# Circuit.net
KiCad netlist of a schematic drawn in EAGLE
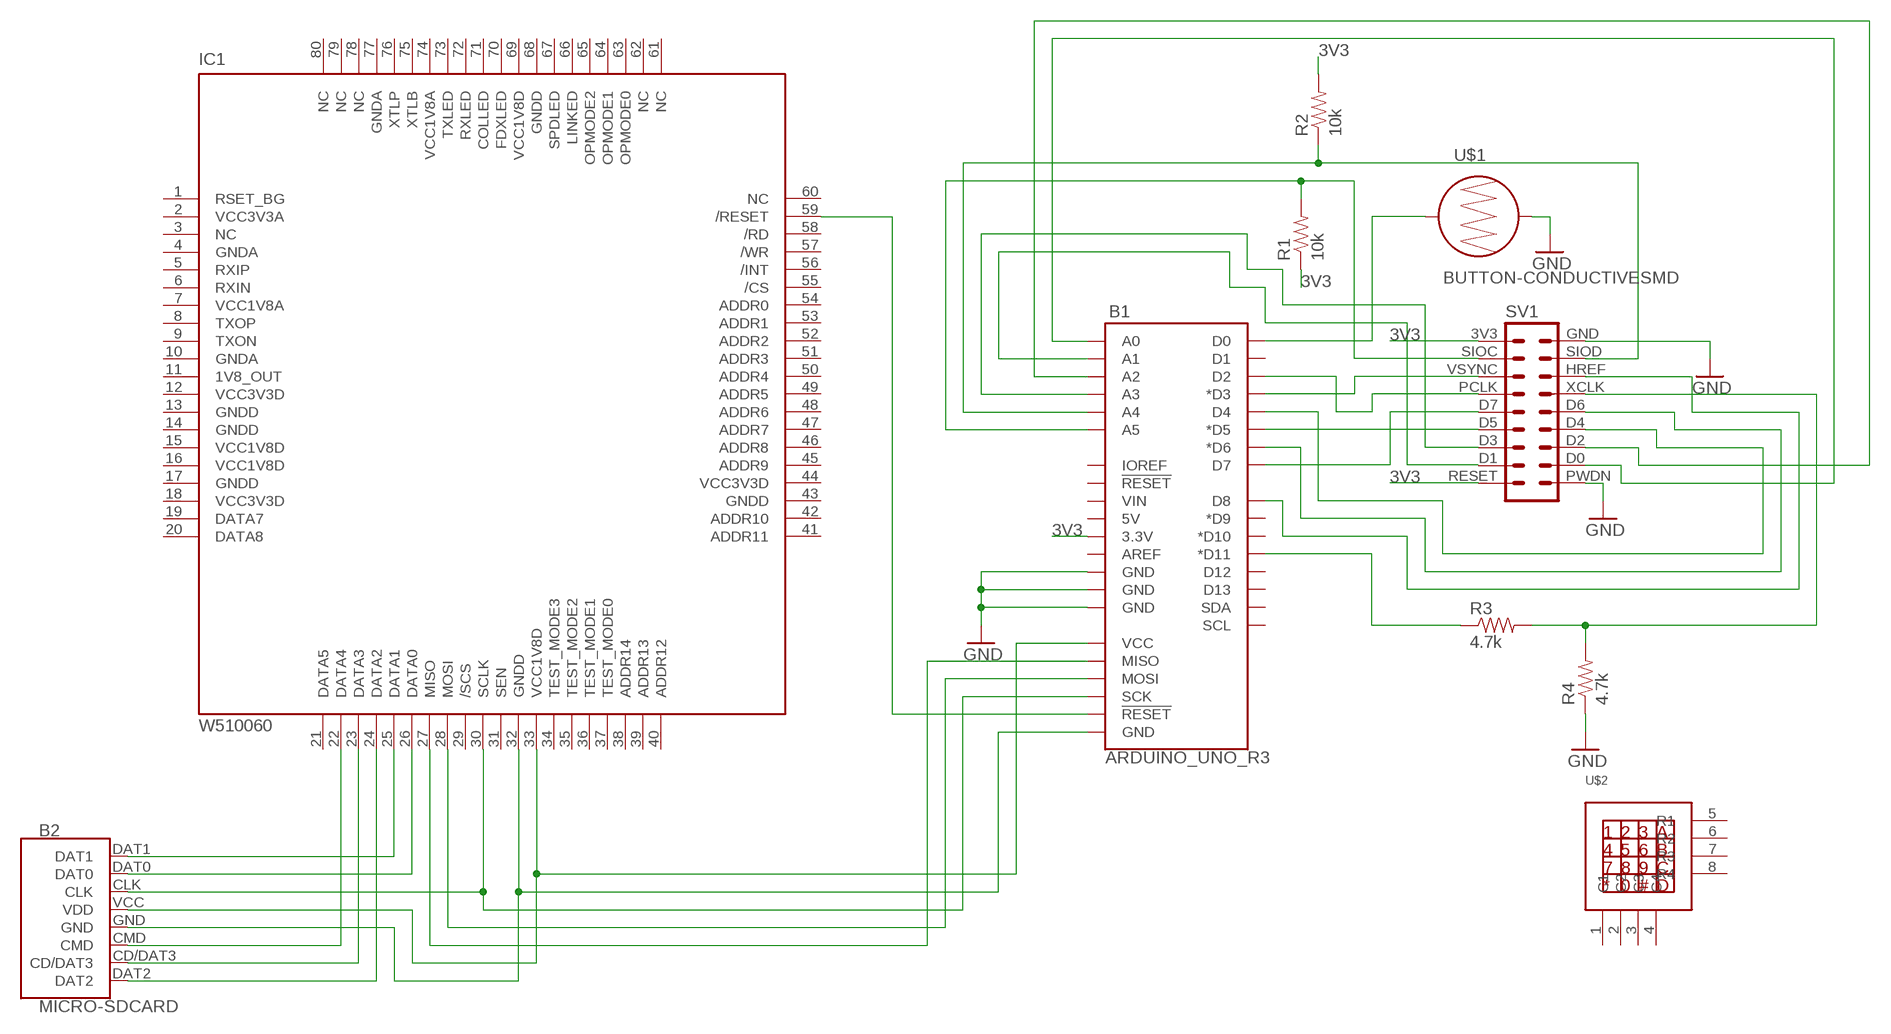
[diagram p0: schematic, sheet 1]

(export (version "E")
  (design (tool "Eeschema 10.0.6"))
  (components
    (comp (ref "B1")
      (value "ARDUINO_UNO_R3")
      (footprint "eagle-import:ARDUINO_R3")
      (libsource (lib "eagle-import") (part "ARDUINO_UNO_R3"))
    )
    (comp (ref "B2")
      (value "MICRO-SDCARD")
      (footprint "eagle-import:MICRO-SDCARD")
      (libsource (lib "eagle-import") (part "MICRO-SDCARD"))
    )
    (comp (ref "IC1")
      (value "W510060")
      (footprint "eagle-import:W5100")
      (fields (field (name "MPN") "PIC18F86J60-I/PT"))
      (libsource (lib "eagle-import") (part "W510006"))
    )
    (comp (ref "R1")
      (value "10k")
      (footprint "eagle-import:0402-RES")
      (libsource (lib "eagle-import") (part "RESISTOR0402"))
    )
    (comp (ref "R2")
      (value "10k")
      (footprint "eagle-import:0402-RES")
      (libsource (lib "eagle-import") (part "RESISTOR0402"))
    )
    (comp (ref "R3")
      (value "4.7k")
      (footprint "eagle-import:0402-RES")
      (libsource (lib "eagle-import") (part "RESISTOR0402"))
    )
    (comp (ref "R4")
      (value "4.7k")
      (footprint "eagle-import:0402-RES")
      (libsource (lib "eagle-import") (part "RESISTOR0402"))
    )
    (comp (ref "SV1")
      (value "ML16L")
      (footprint "eagle-import:ML16L")
      (libsource (lib "eagle-import") (part "ML16L"))
    )
    (comp (ref "U$1")
      (value "BUTTON-CONDUCTIVESMD")
      (footprint "eagle-import:BUTTON-CONDUCTIVE")
      (libsource (lib "eagle-import") (part "BUTTON-CONDUCTIVESMD"))
    )
    (comp (ref "U$2")
      (value "KEYPAD4X4")
      (footprint "eagle-import:KEYPAD4X4")
      (libsource (lib "eagle-import") (part "KEYPAD4X4"))
    )
  )
  (nets
    (net (code "1") (name "/1V8_OUT") (class "Default")
      (node (ref "IC1") (pin "11") (pinfunction "1V8_OUT_11") (pintype "power_in"))
    )
    (net (code "2") (name "/3V3") (class "Default")
      (node (ref "B1") (pin "3.3V") (pinfunction "3.3V_3.3V") (pintype "bidirectional"))
      (node (ref "R1") (pin "1") (pinfunction "1_1") (pintype "passive"))
      (node (ref "R2") (pin "2") (pinfunction "2_2") (pintype "passive"))
      (node (ref "SV1") (pin "3V3") (pinfunction "3V3_3V3") (pintype "passive"))
      (node (ref "SV1") (pin "RESET") (pinfunction "RESET_RESET") (pintype "passive"))
    )
    (net (code "3") (name "/ADDR3") (class "Default")
      (node (ref "IC1") (pin "51") (pinfunction "ADDR3_51") (pintype "power_in"))
    )
    (net (code "4") (name "/ADDR6") (class "Default")
      (node (ref "IC1") (pin "48") (pinfunction "ADDR6_48") (pintype "power_in"))
    )
    (net (code "5") (name "/COLLED") (class "Default")
      (node (ref "IC1") (pin "71") (pinfunction "COLLED_71") (pintype "power_in"))
    )
    (net (code "6") (name "/FDXLED") (class "Default")
      (node (ref "IC1") (pin "70") (pinfunction "FDXLED_70") (pintype "power_in"))
    )
    (net (code "7") (name "/SEN") (class "Default")
      (node (ref "IC1") (pin "31") (pinfunction "SEN_31") (pintype "power_in"))
    )
    (net (code "8") (name "GND") (class "Default")
      (node (ref "B1") (pin "GND@2") (pinfunction "GND_GND@2") (pintype "bidirectional"))
      (node (ref "B1") (pin "GND@3") (pinfunction "GND_GND@3") (pintype "bidirectional"))
      (node (ref "B1") (pin "GND@4") (pinfunction "GND_GND@4") (pintype "bidirectional"))
      (node (ref "R4") (pin "1") (pinfunction "1_1") (pintype "passive"))
      (node (ref "SV1") (pin "GND") (pinfunction "GND_GND") (pintype "passive"))
      (node (ref "SV1") (pin "PWDN") (pinfunction "PWDN_PWDN") (pintype "passive"))
      (node (ref "U$1") (pin "2") (pinfunction "2_2") (pintype "passive"))
    )
    (net (code "9") (name "Net-(B1-*D3)") (class "Default")
      (node (ref "B1") (pin "D3") (pinfunction "*D3_D3") (pintype "bidirectional"))
      (node (ref "SV1") (pin "VSYNC") (pinfunction "VSYNC_VSYNC") (pintype "passive"))
    )
    (net (code "10") (name "Net-(B1-*D5)") (class "Default")
      (node (ref "B1") (pin "D5") (pinfunction "*D5_D5") (pintype "bidirectional"))
      (node (ref "SV1") (pin "D5") (pinfunction "D5_D5") (pintype "passive"))
    )
    (net (code "11") (name "Net-(B1-*D6)") (class "Default")
      (node (ref "B1") (pin "D6") (pinfunction "*D6_D6") (pintype "bidirectional"))
      (node (ref "SV1") (pin "D6") (pinfunction "D6_D6") (pintype "passive"))
    )
    (net (code "12") (name "Net-(B1-*D11)") (class "Default")
      (node (ref "B1") (pin "D11") (pinfunction "*D11_D11") (pintype "bidirectional"))
      (node (ref "R3") (pin "1") (pinfunction "1_1") (pintype "passive"))
    )
    (net (code "13") (name "Net-(B1-GND-PadGND@1)") (class "Default")
      (node (ref "B1") (pin "GND@1") (pinfunction "GND_GND@1") (pintype "bidirectional"))
      (node (ref "B2") (pin "GND") (pinfunction "GND_GND") (pintype "power_in"))
      (node (ref "IC1") (pin "32") (pinfunction "GNDD_32") (pintype "power_in"))
    )
    (net (code "14") (name "Net-(B1-PadA0)") (class "Default")
      (node (ref "B1") (pin "A0") (pinfunction "A0_A0") (pintype "bidirectional"))
      (node (ref "SV1") (pin "D0") (pinfunction "D0_D0") (pintype "passive"))
    )
    (net (code "15") (name "Net-(B1-PadA1)") (class "Default")
      (node (ref "B1") (pin "A1") (pinfunction "A1_A1") (pintype "bidirectional"))
      (node (ref "SV1") (pin "D1") (pinfunction "D1_D1") (pintype "passive"))
    )
    (net (code "16") (name "Net-(B1-PadA2)") (class "Default")
      (node (ref "B1") (pin "A2") (pinfunction "A2_A2") (pintype "bidirectional"))
      (node (ref "SV1") (pin "D2") (pinfunction "D2_D2") (pintype "passive"))
    )
    (net (code "17") (name "Net-(B1-PadA3)") (class "Default")
      (node (ref "B1") (pin "A3") (pinfunction "A3_A3") (pintype "bidirectional"))
      (node (ref "SV1") (pin "D3") (pinfunction "D3_D3") (pintype "passive"))
    )
    (net (code "18") (name "Net-(B1-PadA4)") (class "Default")
      (node (ref "B1") (pin "A4") (pinfunction "A4_A4") (pintype "bidirectional"))
      (node (ref "R2") (pin "1") (pinfunction "1_1") (pintype "passive"))
      (node (ref "SV1") (pin "SIOD") (pinfunction "SIOD_SIOD") (pintype "passive"))
    )
    (net (code "19") (name "Net-(B1-PadA5)") (class "Default")
      (node (ref "B1") (pin "A5") (pinfunction "A5_A5") (pintype "bidirectional"))
      (node (ref "R1") (pin "2") (pinfunction "2_2") (pintype "passive"))
      (node (ref "SV1") (pin "SIOC") (pinfunction "SIOC_SIOC") (pintype "passive"))
    )
    (net (code "20") (name "Net-(B1-PadD0)") (class "Default")
      (node (ref "B1") (pin "D0") (pinfunction "D0_D0") (pintype "bidirectional"))
      (node (ref "U$1") (pin "1") (pinfunction "1_1") (pintype "passive"))
    )
    (net (code "21") (name "Net-(B1-PadD2)") (class "Default")
      (node (ref "B1") (pin "D2") (pinfunction "D2_D2") (pintype "bidirectional"))
      (node (ref "SV1") (pin "PCLK") (pinfunction "PCLK_PCLK") (pintype "passive"))
    )
    (net (code "22") (name "Net-(B1-PadD4)") (class "Default")
      (node (ref "B1") (pin "D4") (pinfunction "D4_D4") (pintype "bidirectional"))
      (node (ref "SV1") (pin "D4") (pinfunction "D4_D4") (pintype "passive"))
    )
    (net (code "23") (name "Net-(B1-PadD7)") (class "Default")
      (node (ref "B1") (pin "D7") (pinfunction "D7_D7") (pintype "bidirectional"))
      (node (ref "SV1") (pin "D7") (pinfunction "D7_D7") (pintype "passive"))
    )
    (net (code "24") (name "Net-(B1-PadD8)") (class "Default")
      (node (ref "B1") (pin "D8") (pinfunction "D8_D8") (pintype "bidirectional"))
      (node (ref "SV1") (pin "HREF") (pinfunction "HREF_HREF") (pintype "passive"))
    )
    (net (code "25") (name "Net-(B2-VDD)") (class "Default")
      (node (ref "B1") (pin "VCC") (pinfunction "VCC_VCC") (pintype "bidirectional"))
      (node (ref "B2") (pin "VCC") (pinfunction "VDD_VCC") (pintype "power_in"))
      (node (ref "IC1") (pin "33") (pinfunction "VCC1V8D_33") (pintype "bidirectional"))
    )
    (net (code "26") (name "Net-(IC1-DATA0)") (class "Default")
      (node (ref "B2") (pin "DAT0") (pinfunction "DAT0_DAT0") (pintype "bidirectional"))
      (node (ref "IC1") (pin "26") (pinfunction "DATA0_26") (pintype "input"))
    )
    (net (code "27") (name "Net-(IC1-DATA1)") (class "Default")
      (node (ref "B2") (pin "DAT1") (pinfunction "DAT1_DAT1") (pintype "bidirectional"))
      (node (ref "IC1") (pin "25") (pinfunction "DATA1_25") (pintype "input"))
    )
    (net (code "28") (name "Net-(IC1-DATA2)") (class "Default")
      (node (ref "B2") (pin "DAT2") (pinfunction "DAT2_DAT2") (pintype "bidirectional"))
      (node (ref "IC1") (pin "24") (pinfunction "DATA2_24") (pintype "input"))
    )
    (net (code "29") (name "Net-(IC1-DATA3)") (class "Default")
      (node (ref "B2") (pin "CD/DAT3") (pinfunction "CD/DAT3_CD/DAT3") (pintype "bidirectional"))
      (node (ref "IC1") (pin "23") (pinfunction "DATA3_23") (pintype "bidirectional"))
    )
    (net (code "30") (name "Net-(IC1-DATA4)") (class "Default")
      (node (ref "B2") (pin "CMD") (pinfunction "CMD_CMD") (pintype "bidirectional"))
      (node (ref "IC1") (pin "22") (pinfunction "DATA4_22") (pintype "bidirectional"))
    )
    (net (code "31") (name "Net-(IC1-MISO)") (class "Default")
      (node (ref "B1") (pin "MISO") (pinfunction "MISO_MISO") (pintype "bidirectional"))
      (node (ref "IC1") (pin "27") (pinfunction "MISO_27") (pintype "bidirectional"))
    )
    (net (code "32") (name "Net-(IC1-MOSI)") (class "Default")
      (node (ref "B1") (pin "MOSI") (pinfunction "MOSI_MOSI") (pintype "bidirectional"))
      (node (ref "IC1") (pin "28") (pinfunction "MOSI_28") (pintype "bidirectional"))
    )
    (net (code "33") (name "Net-(IC1-SCLK)") (class "Default")
      (node (ref "B1") (pin "SCK") (pinfunction "SCK_SCK") (pintype "bidirectional"))
      (node (ref "B2") (pin "CLK") (pinfunction "CLK_CLK") (pintype "bidirectional"))
      (node (ref "IC1") (pin "30") (pinfunction "SCLK_30") (pintype "bidirectional"))
    )
    (net (code "34") (name "Net-(IC1-{slash}RESET)") (class "Default")
      (node (ref "B1") (pin "RESET@2") (pinfunction "~{RESET}_RESET@2") (pintype "bidirectional"))
      (node (ref "IC1") (pin "59") (pinfunction "/RESET_59") (pintype "input"))
    )
    (net (code "35") (name "Net-(R3-Pad2)") (class "Default")
      (node (ref "R3") (pin "2") (pinfunction "2_2") (pintype "passive"))
      (node (ref "R4") (pin "2") (pinfunction "2_2") (pintype "passive"))
      (node (ref "SV1") (pin "XCLK") (pinfunction "XCLK_XCLK") (pintype "passive"))
    )
    (net (code "36") (name "unconnected-(B1-*D9-PadD9)") (class "Default")
      (node (ref "B1") (pin "D9") (pinfunction "*D9_D9") (pintype "bidirectional"))
    )
    (net (code "37") (name "unconnected-(B1-*D10-PadD10)") (class "Default")
      (node (ref "B1") (pin "D10") (pinfunction "*D10_D10") (pintype "bidirectional"))
    )
    (net (code "38") (name "unconnected-(B1-Pad5V)") (class "Default")
      (node (ref "B1") (pin "5V") (pinfunction "5V_5V") (pintype "bidirectional"))
    )
    (net (code "39") (name "unconnected-(B1-PadAREF)") (class "Default")
      (node (ref "B1") (pin "AREF") (pinfunction "AREF_AREF") (pintype "bidirectional"))
    )
    (net (code "40") (name "unconnected-(B1-PadD1)") (class "Default")
      (node (ref "B1") (pin "D1") (pinfunction "D1_D1") (pintype "bidirectional"))
    )
    (net (code "41") (name "unconnected-(B1-PadD12)") (class "Default")
      (node (ref "B1") (pin "D12") (pinfunction "D12_D12") (pintype "bidirectional"))
    )
    (net (code "42") (name "unconnected-(B1-PadD13)") (class "Default")
      (node (ref "B1") (pin "D13") (pinfunction "D13_D13") (pintype "bidirectional"))
    )
    (net (code "43") (name "unconnected-(B1-PadIOREF)") (class "Default")
      (node (ref "B1") (pin "IOREF") (pinfunction "IOREF_IOREF") (pintype "bidirectional"))
    )
    (net (code "44") (name "unconnected-(B1-PadSCL)") (class "Default")
      (node (ref "B1") (pin "SCL") (pinfunction "SCL_SCL") (pintype "bidirectional"))
    )
    (net (code "45") (name "unconnected-(B1-PadSDA)") (class "Default")
      (node (ref "B1") (pin "SDA") (pinfunction "SDA_SDA") (pintype "bidirectional"))
    )
    (net (code "46") (name "unconnected-(B1-PadVIN)") (class "Default")
      (node (ref "B1") (pin "VIN") (pinfunction "VIN_VIN") (pintype "bidirectional"))
    )
    (net (code "47") (name "unconnected-(B1-~{RESET}-PadRESET@1)") (class "Default")
      (node (ref "B1") (pin "RESET@1") (pinfunction "~{RESET}_RESET@1") (pintype "bidirectional"))
    )
    (net (code "48") (name "unconnected-(IC1-ADDR0-Pad54)") (class "Default")
      (node (ref "IC1") (pin "54") (pinfunction "ADDR0_54") (pintype "bidirectional"))
    )
    (net (code "49") (name "unconnected-(IC1-ADDR1-Pad53)") (class "Default")
      (node (ref "IC1") (pin "53") (pinfunction "ADDR1_53") (pintype "bidirectional"))
    )
    (net (code "50") (name "unconnected-(IC1-ADDR2-Pad52)") (class "Default")
      (node (ref "IC1") (pin "52") (pinfunction "ADDR2_52") (pintype "bidirectional"))
    )
    (net (code "51") (name "unconnected-(IC1-ADDR4-Pad50)") (class "Default")
      (node (ref "IC1") (pin "50") (pinfunction "ADDR4_50") (pintype "output"))
    )
    (net (code "52") (name "unconnected-(IC1-ADDR5-Pad49)") (class "Default")
      (node (ref "IC1") (pin "49") (pinfunction "ADDR5_49") (pintype "input"))
    )
    (net (code "53") (name "unconnected-(IC1-ADDR7-Pad47)") (class "Default")
      (node (ref "IC1") (pin "47") (pinfunction "ADDR7_47") (pintype "bidirectional"))
    )
    (net (code "54") (name "unconnected-(IC1-ADDR8-Pad46)") (class "Default")
      (node (ref "IC1") (pin "46") (pinfunction "ADDR8_46") (pintype "bidirectional"))
    )
    (net (code "55") (name "unconnected-(IC1-ADDR9-Pad45)") (class "Default")
      (node (ref "IC1") (pin "45") (pinfunction "ADDR9_45") (pintype "bidirectional"))
    )
    (net (code "56") (name "unconnected-(IC1-ADDR10-Pad42)") (class "Default")
      (node (ref "IC1") (pin "42") (pinfunction "ADDR10_42") (pintype "bidirectional"))
    )
    (net (code "57") (name "unconnected-(IC1-ADDR11-Pad41)") (class "Default")
      (node (ref "IC1") (pin "41") (pinfunction "ADDR11_41") (pintype "bidirectional"))
    )
    (net (code "58") (name "unconnected-(IC1-ADDR12-Pad40)") (class "Default")
      (node (ref "IC1") (pin "40") (pinfunction "ADDR12_40") (pintype "bidirectional"))
    )
    (net (code "59") (name "unconnected-(IC1-ADDR13-Pad39)") (class "Default")
      (node (ref "IC1") (pin "39") (pinfunction "ADDR13_39") (pintype "bidirectional"))
    )
    (net (code "60") (name "unconnected-(IC1-ADDR14-Pad38)") (class "Default")
      (node (ref "IC1") (pin "38") (pinfunction "ADDR14_38") (pintype "bidirectional"))
    )
    (net (code "61") (name "unconnected-(IC1-DATA5-Pad21)") (class "Default")
      (node (ref "IC1") (pin "21") (pinfunction "DATA5_21") (pintype "bidirectional"))
    )
    (net (code "62") (name "unconnected-(IC1-DATA7-Pad19)") (class "Default")
      (node (ref "IC1") (pin "19") (pinfunction "DATA7_19") (pintype "bidirectional"))
    )
    (net (code "63") (name "unconnected-(IC1-DATA8-Pad20)") (class "Default")
      (node (ref "IC1") (pin "20") (pinfunction "DATA8_20") (pintype "bidirectional"))
    )
    (net (code "64") (name "unconnected-(IC1-GNDA-Pad4)") (class "Default")
      (node (ref "IC1") (pin "4") (pinfunction "GNDA_4") (pintype "bidirectional"))
    )
    (net (code "65") (name "unconnected-(IC1-GNDA-Pad10)") (class "Default")
      (node (ref "IC1") (pin "10") (pinfunction "GNDA_10") (pintype "bidirectional"))
    )
    (net (code "66") (name "unconnected-(IC1-GNDA-Pad77)") (class "Default")
      (node (ref "IC1") (pin "77") (pinfunction "GNDA_77") (pintype "bidirectional"))
    )
    (net (code "67") (name "unconnected-(IC1-GNDD-Pad13)") (class "Default")
      (node (ref "IC1") (pin "13") (pinfunction "GNDD_13") (pintype "bidirectional"))
    )
    (net (code "68") (name "unconnected-(IC1-GNDD-Pad14)") (class "Default")
      (node (ref "IC1") (pin "14") (pinfunction "GNDD_14") (pintype "bidirectional"))
    )
    (net (code "69") (name "unconnected-(IC1-GNDD-Pad17)") (class "Default")
      (node (ref "IC1") (pin "17") (pinfunction "GNDD_17") (pintype "bidirectional"))
    )
    (net (code "70") (name "unconnected-(IC1-GNDD-Pad43)") (class "Default")
      (node (ref "IC1") (pin "43") (pinfunction "GNDD_43") (pintype "bidirectional"))
    )
    (net (code "71") (name "unconnected-(IC1-GNDD-Pad68)") (class "Default")
      (node (ref "IC1") (pin "68") (pinfunction "GNDD_68") (pintype "bidirectional"))
    )
    (net (code "72") (name "unconnected-(IC1-LINKED-Pad66)") (class "Default")
      (node (ref "IC1") (pin "66") (pinfunction "LINKED_66") (pintype "input"))
    )
    (net (code "73") (name "unconnected-(IC1-NC-Pad3)") (class "Default")
      (node (ref "IC1") (pin "3") (pinfunction "NC_3") (pintype "bidirectional"))
    )
    (net (code "74") (name "unconnected-(IC1-NC-Pad60)") (class "Default")
      (node (ref "IC1") (pin "60") (pinfunction "NC_60") (pintype "input"))
    )
    (net (code "75") (name "unconnected-(IC1-NC-Pad61)") (class "Default")
      (node (ref "IC1") (pin "61") (pinfunction "NC_61") (pintype "input"))
    )
    (net (code "76") (name "unconnected-(IC1-NC-Pad62)") (class "Default")
      (node (ref "IC1") (pin "62") (pinfunction "NC_62") (pintype "output"))
    )
    (net (code "77") (name "unconnected-(IC1-NC-Pad78)") (class "Default")
      (node (ref "IC1") (pin "78") (pinfunction "NC_78") (pintype "bidirectional"))
    )
    (net (code "78") (name "unconnected-(IC1-NC-Pad79)") (class "Default")
      (node (ref "IC1") (pin "79") (pinfunction "NC_79") (pintype "bidirectional"))
    )
    (net (code "79") (name "unconnected-(IC1-NC-Pad80)") (class "Default")
      (node (ref "IC1") (pin "80") (pinfunction "NC_80") (pintype "bidirectional"))
    )
    (net (code "80") (name "unconnected-(IC1-OPMODE0-Pad63)") (class "Default")
      (node (ref "IC1") (pin "63") (pinfunction "OPMODE0_63") (pintype "output"))
    )
    (net (code "81") (name "unconnected-(IC1-OPMODE1-Pad64)") (class "Default")
      (node (ref "IC1") (pin "64") (pinfunction "OPMODE1_64") (pintype "input"))
    )
    (net (code "82") (name "unconnected-(IC1-OPMODE2-Pad65)") (class "Default")
      (node (ref "IC1") (pin "65") (pinfunction "OPMODE2_65") (pintype "input"))
    )
    (net (code "83") (name "unconnected-(IC1-RSET_BG-Pad1)") (class "Default")
      (node (ref "IC1") (pin "1") (pinfunction "RSET_BG_1") (pintype "bidirectional"))
    )
    (net (code "84") (name "unconnected-(IC1-RXIN-Pad6)") (class "Default")
      (node (ref "IC1") (pin "6") (pinfunction "RXIN_6") (pintype "bidirectional"))
    )
    (net (code "85") (name "unconnected-(IC1-RXIP-Pad5)") (class "Default")
      (node (ref "IC1") (pin "5") (pinfunction "RXIP_5") (pintype "bidirectional"))
    )
    (net (code "86") (name "unconnected-(IC1-RXLED-Pad72)") (class "Default")
      (node (ref "IC1") (pin "72") (pinfunction "RXLED_72") (pintype "bidirectional"))
    )
    (net (code "87") (name "unconnected-(IC1-SPDLED-Pad67)") (class "Default")
      (node (ref "IC1") (pin "67") (pinfunction "SPDLED_67") (pintype "input"))
    )
    (net (code "88") (name "unconnected-(IC1-TEST_MODE0-Pad37)") (class "Default")
      (node (ref "IC1") (pin "37") (pinfunction "TEST_MODE0_37") (pintype "bidirectional"))
    )
    (net (code "89") (name "unconnected-(IC1-TEST_MODE1-Pad36)") (class "Default")
      (node (ref "IC1") (pin "36") (pinfunction "TEST_MODE1_36") (pintype "bidirectional"))
    )
    (net (code "90") (name "unconnected-(IC1-TEST_MODE2-Pad35)") (class "Default")
      (node (ref "IC1") (pin "35") (pinfunction "TEST_MODE2_35") (pintype "bidirectional"))
    )
    (net (code "91") (name "unconnected-(IC1-TEST_MODE3-Pad34)") (class "Default")
      (node (ref "IC1") (pin "34") (pinfunction "TEST_MODE3_34") (pintype "bidirectional"))
    )
    (net (code "92") (name "unconnected-(IC1-TXLED-Pad73)") (class "Default")
      (node (ref "IC1") (pin "73") (pinfunction "TXLED_73") (pintype "bidirectional"))
    )
    (net (code "93") (name "unconnected-(IC1-TXON-Pad9)") (class "Default")
      (node (ref "IC1") (pin "9") (pinfunction "TXON_9") (pintype "input"))
    )
    (net (code "94") (name "unconnected-(IC1-TXOP-Pad8)") (class "Default")
      (node (ref "IC1") (pin "8") (pinfunction "TXOP_8") (pintype "bidirectional"))
    )
    (net (code "95") (name "unconnected-(IC1-VCC1V8A-Pad7)") (class "Default")
      (node (ref "IC1") (pin "7") (pinfunction "VCC1V8A_7") (pintype "bidirectional"))
    )
    (net (code "96") (name "unconnected-(IC1-VCC1V8A-Pad74)") (class "Default")
      (node (ref "IC1") (pin "74") (pinfunction "VCC1V8A_74") (pintype "bidirectional"))
    )
    (net (code "97") (name "unconnected-(IC1-VCC1V8D-Pad15)") (class "Default")
      (node (ref "IC1") (pin "15") (pinfunction "VCC1V8D_15") (pintype "bidirectional"))
    )
    (net (code "98") (name "unconnected-(IC1-VCC1V8D-Pad16)") (class "Default")
      (node (ref "IC1") (pin "16") (pinfunction "VCC1V8D_16") (pintype "bidirectional"))
    )
    (net (code "99") (name "unconnected-(IC1-VCC1V8D-Pad69)") (class "Default")
      (node (ref "IC1") (pin "69") (pinfunction "VCC1V8D_69") (pintype "bidirectional"))
    )
    (net (code "100") (name "unconnected-(IC1-VCC3V3A-Pad2)") (class "Default")
      (node (ref "IC1") (pin "2") (pinfunction "VCC3V3A_2") (pintype "bidirectional"))
    )
    (net (code "101") (name "unconnected-(IC1-VCC3V3D-Pad12)") (class "Default")
      (node (ref "IC1") (pin "12") (pinfunction "VCC3V3D_12") (pintype "input"))
    )
    (net (code "102") (name "unconnected-(IC1-VCC3V3D-Pad18)") (class "Default")
      (node (ref "IC1") (pin "18") (pinfunction "VCC3V3D_18") (pintype "bidirectional"))
    )
    (net (code "103") (name "unconnected-(IC1-VCC3V3D-Pad44)") (class "Default")
      (node (ref "IC1") (pin "44") (pinfunction "VCC3V3D_44") (pintype "bidirectional"))
    )
    (net (code "104") (name "unconnected-(IC1-XTLB-Pad75)") (class "Default")
      (node (ref "IC1") (pin "75") (pinfunction "XTLB_75") (pintype "bidirectional"))
    )
    (net (code "105") (name "unconnected-(IC1-XTLP-Pad76)") (class "Default")
      (node (ref "IC1") (pin "76") (pinfunction "XTLP_76") (pintype "bidirectional"))
    )
    (net (code "106") (name "unconnected-(IC1-{slash}CS-Pad55)") (class "Default")
      (node (ref "IC1") (pin "55") (pinfunction "/CS_55") (pintype "bidirectional"))
    )
    (net (code "107") (name "unconnected-(IC1-{slash}INT-Pad56)") (class "Default")
      (node (ref "IC1") (pin "56") (pinfunction "/INT_56") (pintype "bidirectional"))
    )
    (net (code "108") (name "unconnected-(IC1-{slash}RD-Pad58)") (class "Default")
      (node (ref "IC1") (pin "58") (pinfunction "/RD_58") (pintype "input"))
    )
    (net (code "109") (name "unconnected-(IC1-{slash}SCS-Pad29)") (class "Default")
      (node (ref "IC1") (pin "29") (pinfunction "/SCS_29") (pintype "bidirectional"))
    )
    (net (code "110") (name "unconnected-(IC1-{slash}WR-Pad57)") (class "Default")
      (node (ref "IC1") (pin "57") (pinfunction "/WR_57") (pintype "input"))
    )
    (net (code "111") (name "unconnected-(U$2-C1-Pad1)") (class "Default")
      (node (ref "U$2") (pin "1") (pinfunction "C1_1") (pintype "bidirectional"))
    )
    (net (code "112") (name "unconnected-(U$2-C2-Pad2)") (class "Default")
      (node (ref "U$2") (pin "2") (pinfunction "C2_2") (pintype "bidirectional"))
    )
    (net (code "113") (name "unconnected-(U$2-C3-Pad3)") (class "Default")
      (node (ref "U$2") (pin "3") (pinfunction "C3_3") (pintype "bidirectional"))
    )
    (net (code "114") (name "unconnected-(U$2-C4-Pad4)") (class "Default")
      (node (ref "U$2") (pin "4") (pinfunction "C4_4") (pintype "bidirectional"))
    )
    (net (code "115") (name "unconnected-(U$2-R1-Pad5)") (class "Default")
      (node (ref "U$2") (pin "5") (pinfunction "R1_5") (pintype "bidirectional"))
    )
    (net (code "116") (name "unconnected-(U$2-R2-Pad6)") (class "Default")
      (node (ref "U$2") (pin "6") (pinfunction "R2_6") (pintype "bidirectional"))
    )
    (net (code "117") (name "unconnected-(U$2-R3-Pad7)") (class "Default")
      (node (ref "U$2") (pin "7") (pinfunction "R3_7") (pintype "bidirectional"))
    )
    (net (code "118") (name "unconnected-(U$2-R4-Pad8)") (class "Default")
      (node (ref "U$2") (pin "8") (pinfunction "R4_8") (pintype "bidirectional"))
    )
  )
)
